# EDS_Board_v2.net
KiCad netlist of a schematic drawn in EAGLE
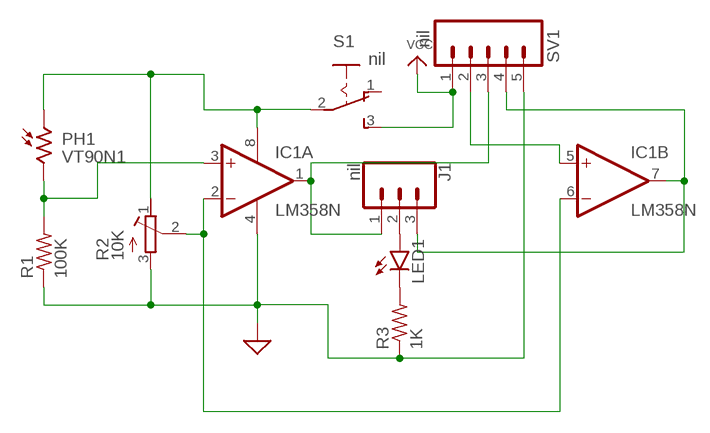
[diagram p0: schematic, sheet 1]

(export (version "E")
  (design (tool "Eeschema 10.0.6"))
  (components
    (comp (ref "IC1")
      (value "LM358N")
      (footprint "eagle-import:DIL08")
      (libsource (lib "eagle-import") (part "LM358N"))
    )
    (comp (ref "J1")
      (value "nil")
      (footprint "eagle-import:1X03")
      (libsource (lib "eagle-import") (part "CONN_03"))
    )
    (comp (ref "LED1")
      (value "RED")
      (footprint "eagle-import:LED5MM")
      (libsource (lib "eagle-import") (part "LED5MM"))
    )
    (comp (ref "PH1")
      (value "VT90N1")
      (footprint "eagle-import:VT900")
      (libsource (lib "eagle-import") (part "VT90N1"))
    )
    (comp (ref "R1")
      (value "100K")
      (footprint "eagle-import:0207_7")
      (libsource (lib "eagle-import") (part "R-US_0207/7"))
    )
    (comp (ref "R2")
      (value "10K")
      (footprint "eagle-import:RTRIMT93YA")
      (libsource (lib "eagle-import") (part "R-TRIMMT93YA"))
    )
    (comp (ref "R3")
      (value "1K")
      (footprint "eagle-import:0207_7")
      (libsource (lib "eagle-import") (part "R-US_0207/7"))
    )
    (comp (ref "S1")
      (value "nil")
      (footprint "eagle-import:255SB")
      (libsource (lib "eagle-import") (part "255SB"))
    )
    (comp (ref "SV1")
      (value "nil")
      (footprint "eagle-import:1X05")
      (libsource (lib "eagle-import") (part "CONN_05"))
    )
  )
  (nets
    (net (code "1") (name "Net-(IC1A-+IN)") (class "Default")
      (node (ref "IC1") (pin "3") (pinfunction "+IN_3") (pintype "input"))
      (node (ref "PH1") (pin "2") (pinfunction "2_2") (pintype "passive"))
      (node (ref "R1") (pin "2") (pinfunction "2_2") (pintype "passive"))
    )
    (net (code "2") (name "Net-(IC1A--IN)") (class "Default")
      (node (ref "IC1") (pin "2") (pinfunction "-IN_2") (pintype "input"))
      (node (ref "IC1") (pin "6") (pinfunction "-IN_6") (pintype "input"))
      (node (ref "R2") (pin "2") (pinfunction "S_2") (pintype "passive"))
    )
    (net (code "3") (name "Net-(IC1A-OUT)") (class "Default")
      (node (ref "IC1") (pin "1") (pinfunction "OUT_1") (pintype "output"))
      (node (ref "J1") (pin "1") (pinfunction "1_1") (pintype "passive"))
      (node (ref "SV1") (pin "3") (pinfunction "3_3") (pintype "passive"))
    )
    (net (code "4") (name "Net-(IC1B-+IN)") (class "Default")
      (node (ref "IC1") (pin "5") (pinfunction "+IN_5") (pintype "input"))
      (node (ref "SV1") (pin "2") (pinfunction "2_2") (pintype "passive"))
    )
    (net (code "5") (name "Net-(IC1B-OUT)") (class "Default")
      (node (ref "IC1") (pin "7") (pinfunction "OUT_7") (pintype "output"))
      (node (ref "J1") (pin "3") (pinfunction "3_3") (pintype "passive"))
      (node (ref "SV1") (pin "4") (pinfunction "4_4") (pintype "passive"))
    )
    (net (code "6") (name "Net-(IC1C-V+)") (class "Default")
      (node (ref "IC1") (pin "8") (pinfunction "V+_8") (pintype "power_in"))
      (node (ref "PH1") (pin "1") (pinfunction "1_1") (pintype "passive"))
      (node (ref "R2") (pin "1") (pinfunction "E_1") (pintype "passive"))
      (node (ref "S1") (pin "2") (pinfunction "P_2") (pintype "passive"))
    )
    (net (code "7") (name "Net-(J1-Pad2)") (class "Default")
      (node (ref "J1") (pin "2") (pinfunction "2_2") (pintype "passive"))
      (node (ref "LED1") (pin "A") (pinfunction "A_A") (pintype "passive"))
    )
    (net (code "8") (name "Net-(LED1-C)") (class "Default")
      (node (ref "LED1") (pin "K") (pinfunction "C_K") (pintype "passive"))
      (node (ref "R3") (pin "2") (pinfunction "2_2") (pintype "passive"))
    )
    (net (code "9") (name "SUP") (class "Default")
      (node (ref "IC1") (pin "4") (pinfunction "V-_4") (pintype "power_in"))
      (node (ref "R1") (pin "1") (pinfunction "1_1") (pintype "passive"))
      (node (ref "R2") (pin "3") (pinfunction "A_3") (pintype "passive"))
      (node (ref "R3") (pin "1") (pinfunction "1_1") (pintype "passive"))
      (node (ref "SV1") (pin "5") (pinfunction "5_5") (pintype "passive"))
    )
    (net (code "10") (name "VCC") (class "Default")
      (node (ref "S1") (pin "3") (pinfunction "S_3") (pintype "passive"))
      (node (ref "SV1") (pin "1") (pinfunction "1_1") (pintype "passive"))
    )
    (net (code "11") (name "unconnected-(S1-O-Pad1)") (class "Default")
      (node (ref "S1") (pin "1") (pinfunction "O_1") (pintype "passive"))
    )
  )
)
